# roller-shutter-controller.net
KiCad netlist of a schematic drawn in EAGLE
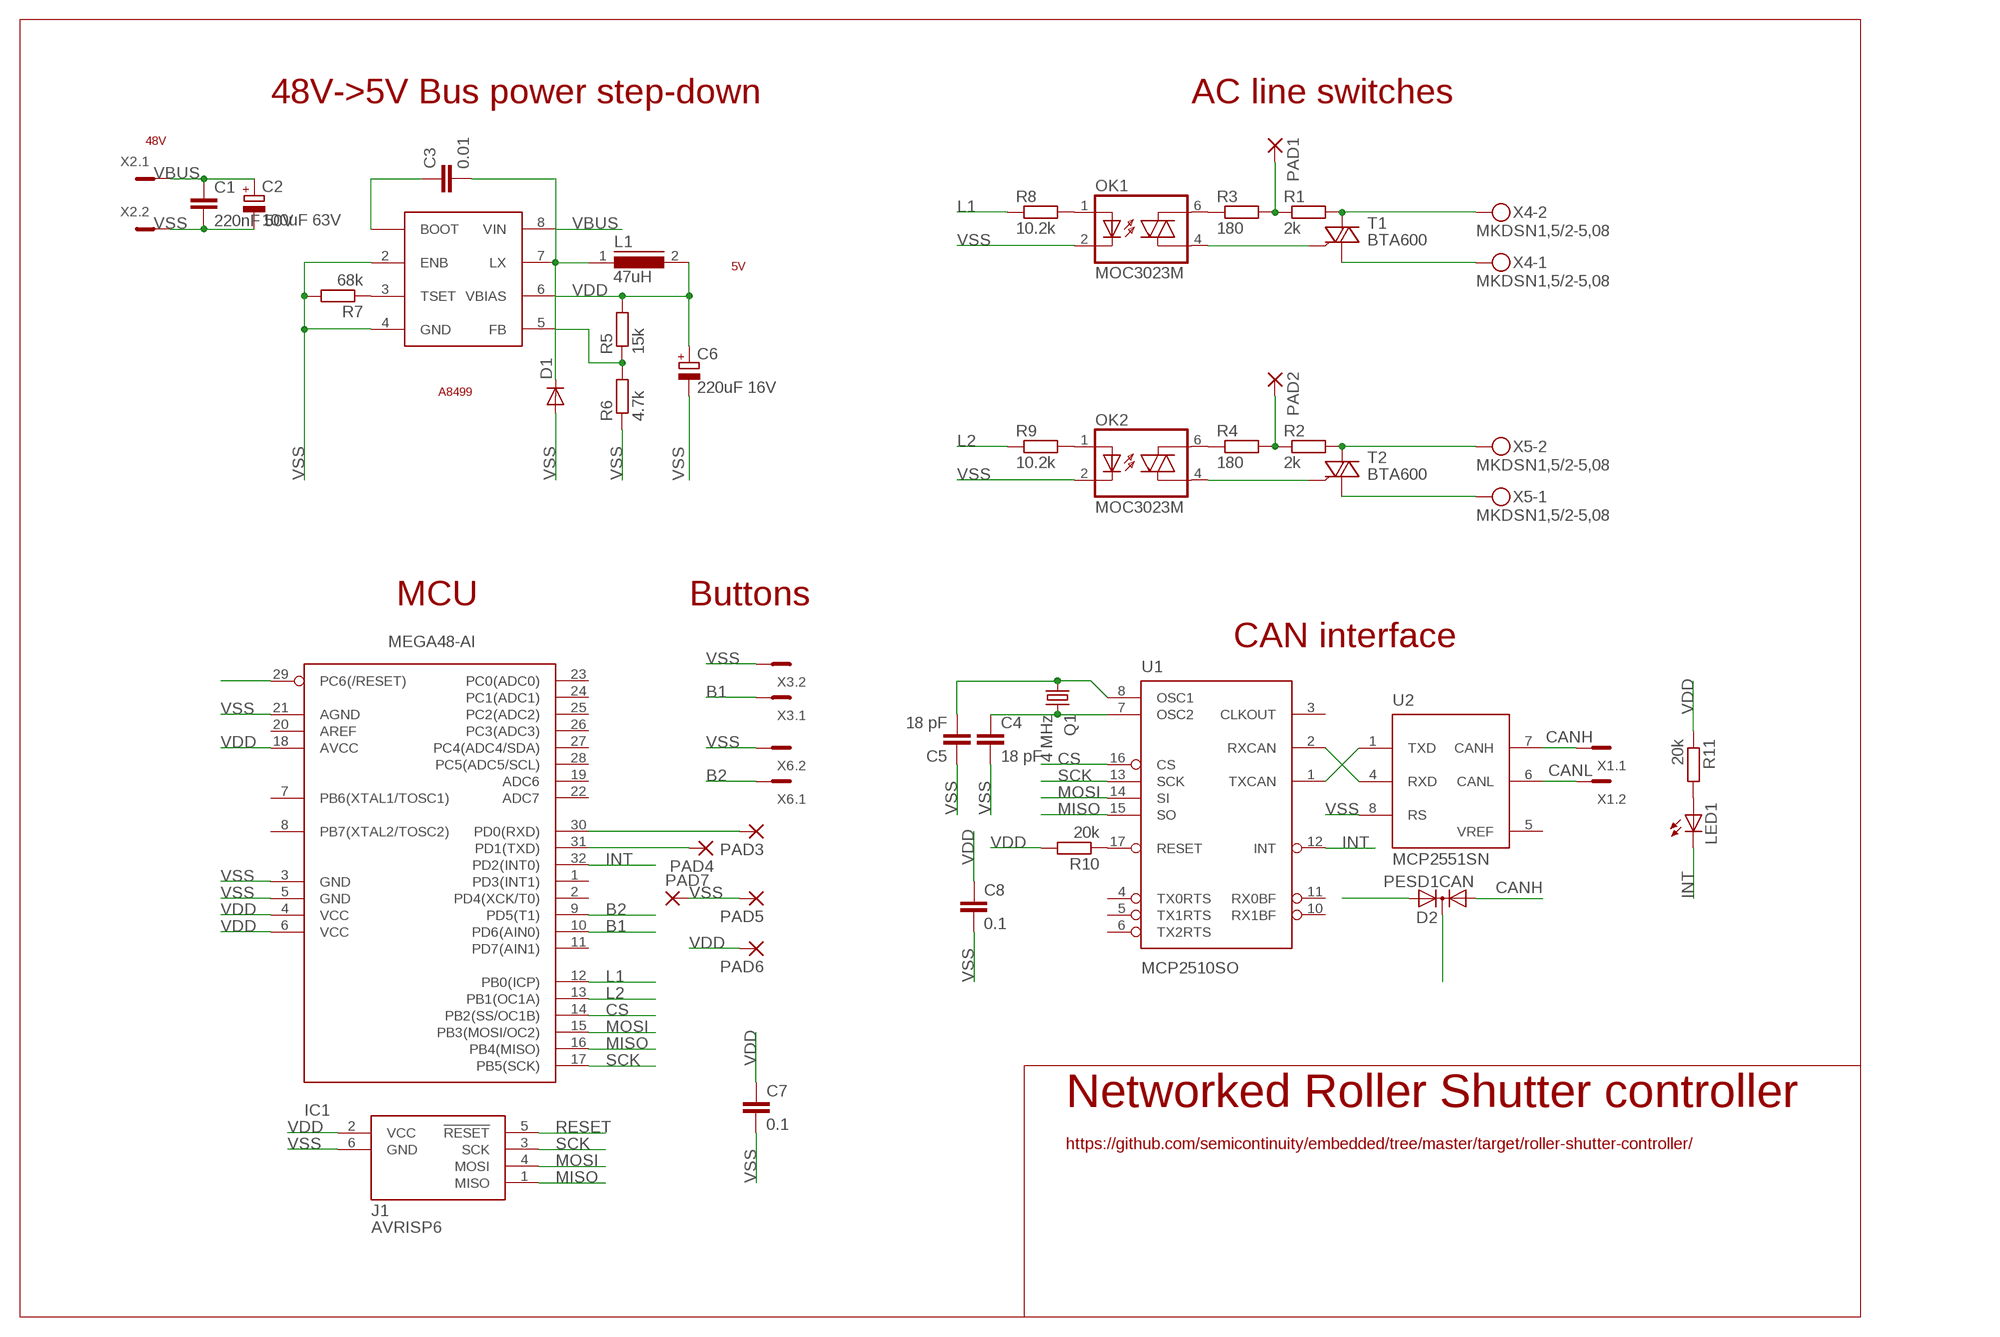
[diagram p0: schematic, sheet 1]

(export (version "E")
  (design (tool "Eeschema 10.0.6"))
  (components
    (comp (ref "C1")
      (value "220nF 50V")
      (footprint "eagle-import:C0805")
      (libsource (lib "eagle-import") (part "C-EUC0805"))
    )
    (comp (ref "C2")
      (value "100uF 63V")
      (footprint "eagle-import:153CLV-1010")
      (libsource (lib "eagle-import") (part "CPOL-EU153CLV-1010"))
    )
    (comp (ref "C3")
      (value "0.01")
      (footprint "eagle-import:C0805")
      (libsource (lib "eagle-import") (part "C-EUC0805"))
    )
    (comp (ref "C4")
      (value "18 pF")
      (footprint "eagle-import:C0805")
      (libsource (lib "eagle-import") (part "C-EUC0805"))
    )
    (comp (ref "C5")
      (value "18 pF")
      (footprint "eagle-import:C0805")
      (libsource (lib "eagle-import") (part "C-EUC0805"))
    )
    (comp (ref "C6")
      (value "220uF 16V")
      (footprint "eagle-import:153CLV-0605")
      (libsource (lib "eagle-import") (part "CPOL-EU153CLV-0605"))
    )
    (comp (ref "C7")
      (value "0.1")
      (footprint "eagle-import:C0805")
      (libsource (lib "eagle-import") (part "C-EUC0805"))
    )
    (comp (ref "C8")
      (value "0.1")
      (footprint "eagle-import:C0805")
      (libsource (lib "eagle-import") (part "C-EUC0805"))
    )
    (comp (ref "D1")
      (value "DIODE-SMB")
      (footprint "eagle-import:SMB")
      (libsource (lib "eagle-import") (part "DIODE-SMB"))
    )
    (comp (ref "D2")
      (value "PESD1CAN")
      (footprint "eagle-import:SOT323")
      (libsource (lib "eagle-import") (part "DIODEA2KSOT323"))
    )
    (comp (ref "IC1")
      (value "MEGA48-AI")
      (footprint "eagle-import:TQFP32-08")
      (libsource (lib "eagle-import") (part "MEGA8-AI"))
    )
    (comp (ref "J1")
      (value "AVRISP6")
      (footprint "eagle-import:CON6P2R")
      (libsource (lib "eagle-import") (part "AVRISP6"))
    )
    (comp (ref "L1")
      (value "47uH")
      (footprint "eagle-import:DR127")
      (libsource (lib "eagle-import") (part "DR127"))
    )
    (comp (ref "LED1")
      (value "LEDCHIP-LED0805")
      (footprint "eagle-import:CHIP-LED0805")
      (libsource (lib "eagle-import") (part "LEDCHIP-LED0805"))
    )
    (comp (ref "OK1")
      (value "MOC3023M")
      (footprint "eagle-import:DIL06")
      (libsource (lib "eagle-import") (part "MOC30M23"))
    )
    (comp (ref "OK2")
      (value "MOC3023M")
      (footprint "eagle-import:DIL06")
      (libsource (lib "eagle-import") (part "MOC30M23"))
    )
    (comp (ref "PAD1")
      (value "1,6/0,8")
      (footprint "eagle-import:1,6_0,8")
      (libsource (lib "eagle-import") (part "1,6/0,8"))
    )
    (comp (ref "PAD2")
      (value "1,6/0,8")
      (footprint "eagle-import:1,6_0,8")
      (libsource (lib "eagle-import") (part "1,6/0,8"))
    )
    (comp (ref "PAD3")
      (value "1,6/0,8")
      (footprint "eagle-import:1,6_0,8")
      (libsource (lib "eagle-import") (part "1,6/0,8"))
    )
    (comp (ref "PAD4")
      (value "1,6/0,8")
      (footprint "eagle-import:1,6_0,8")
      (libsource (lib "eagle-import") (part "1,6/0,8"))
    )
    (comp (ref "PAD5")
      (value "1,6/0,8")
      (footprint "eagle-import:1,6_0,8")
      (libsource (lib "eagle-import") (part "1,6/0,8"))
    )
    (comp (ref "PAD6")
      (value "1,6/0,8")
      (footprint "eagle-import:1,6_0,8")
      (libsource (lib "eagle-import") (part "1,6/0,8"))
    )
    (comp (ref "PAD7")
      (value "1,6/0,8")
      (footprint "eagle-import:1,6_0,8")
      (libsource (lib "eagle-import") (part "1,6/0,8"))
    )
    (comp (ref "Q1")
      (value "4 MHz")
      (footprint "eagle-import:HC49_S")
      (libsource (lib "eagle-import") (part "CRYSTALHC49S"))
    )
    (comp (ref "R1")
      (value "2k")
      (footprint "eagle-import:M0805")
      (libsource (lib "eagle-import") (part "R-EU_M0805"))
    )
    (comp (ref "R2")
      (value "2k")
      (footprint "eagle-import:M0805")
      (libsource (lib "eagle-import") (part "R-EU_M0805"))
    )
    (comp (ref "R3")
      (value "180")
      (footprint "eagle-import:M0805")
      (libsource (lib "eagle-import") (part "R-EU_M0805"))
    )
    (comp (ref "R4")
      (value "180")
      (footprint "eagle-import:M0805")
      (libsource (lib "eagle-import") (part "R-EU_M0805"))
    )
    (comp (ref "R5")
      (value "15k")
      (footprint "eagle-import:R0805")
      (libsource (lib "eagle-import") (part "R-EU_R0805"))
    )
    (comp (ref "R6")
      (value "4.7k")
      (footprint "eagle-import:R0805")
      (libsource (lib "eagle-import") (part "R-EU_R0805"))
    )
    (comp (ref "R7")
      (value "68k")
      (footprint "eagle-import:R0805")
      (libsource (lib "eagle-import") (part "R-EU_R0805"))
    )
    (comp (ref "R8")
      (value "10.2k")
      (footprint "eagle-import:R0805")
      (libsource (lib "eagle-import") (part "R-EU_R0805"))
    )
    (comp (ref "R9")
      (value "10.2k")
      (footprint "eagle-import:R0805")
      (libsource (lib "eagle-import") (part "R-EU_R0805"))
    )
    (comp (ref "R10")
      (value "20k")
      (footprint "eagle-import:R0805")
      (libsource (lib "eagle-import") (part "R-EU_R0805"))
    )
    (comp (ref "R11")
      (value "20k")
      (footprint "eagle-import:R0805")
      (libsource (lib "eagle-import") (part "R-EU_R0805"))
    )
    (comp (ref "T1")
      (value "BTA600")
      (footprint "eagle-import:TO220DS")
      (libsource (lib "eagle-import") (part "TIC225S"))
    )
    (comp (ref "T2")
      (value "BTA600")
      (footprint "eagle-import:TO220DS")
      (libsource (lib "eagle-import") (part "TIC225S"))
    )
    (comp (ref "U$1")
      (value "A8499")
      (footprint "eagle-import:SO08")
      (libsource (lib "eagle-import") (part "A8499SLJT"))
    )
    (comp (ref "U1")
      (value "MCP2510SO")
      (footprint "eagle-import:SO-18W")
      (libsource (lib "eagle-import") (part "MCP2510SO"))
    )
    (comp (ref "U2")
      (value "MCP2551SN")
      (footprint "eagle-import:SO-08")
      (libsource (lib "eagle-import") (part "MCP2551SN"))
    )
    (comp (ref "X1")
      (value "MCV2")
      (footprint "eagle-import:MCV2")
      (libsource (lib "eagle-import") (part "MCV2"))
    )
    (comp (ref "X2")
      (value "MCV2")
      (footprint "eagle-import:MCV2")
      (libsource (lib "eagle-import") (part "MCV2"))
    )
    (comp (ref "X3")
      (value "MCV2")
      (footprint "eagle-import:MCV2")
      (libsource (lib "eagle-import") (part "MCV2"))
    )
    (comp (ref "X4")
      (value "MKDSN1,5/2-5,08")
      (footprint "eagle-import:MKDSN1,5_2-5,08")
      (fields (field (name "MPN") "MKDSN 1,5/2-5.08"))
      (libsource (lib "eagle-import") (part "MKDSN1,5/2-5,08"))
    )
    (comp (ref "X5")
      (value "MKDSN1,5/2-5,08")
      (footprint "eagle-import:MKDSN1,5_2-5,08")
      (fields (field (name "MPN") "MKDSN 1,5/2-5.08"))
      (libsource (lib "eagle-import") (part "MKDSN1,5/2-5,08"))
    )
    (comp (ref "X6")
      (value "MCV2")
      (footprint "eagle-import:MCV2")
      (libsource (lib "eagle-import") (part "MCV2"))
    )
  )
  (nets
    (net (code "1") (name "/B1") (class "Default")
      (node (ref "IC1") (pin "10") (pinfunction "PD6(AIN0)_10") (pintype "bidirectional"))
      (node (ref "X3") (pin "1") (pinfunction "SK_1") (pintype "passive"))
    )
    (net (code "2") (name "/B2") (class "Default")
      (node (ref "IC1") (pin "9") (pinfunction "PD5(T1)_9") (pintype "bidirectional"))
      (node (ref "X6") (pin "1") (pinfunction "SK_1") (pintype "passive"))
    )
    (net (code "3") (name "/CANH") (class "Default")
      (node (ref "D2") (pin "1") (pinfunction "A1_1") (pintype "passive"))
      (node (ref "U2") (pin "7") (pinfunction "CANH_7") (pintype "bidirectional"))
      (node (ref "X1") (pin "1") (pinfunction "SK_1") (pintype "passive"))
    )
    (net (code "4") (name "/CANL") (class "Default")
      (node (ref "D2") (pin "2") (pinfunction "A2_2") (pintype "passive"))
      (node (ref "U2") (pin "6") (pinfunction "CANL_6") (pintype "bidirectional"))
      (node (ref "X1") (pin "2") (pinfunction "SK_2") (pintype "passive"))
    )
    (net (code "5") (name "/CS") (class "Default")
      (node (ref "IC1") (pin "14") (pinfunction "PB2(SS/OC1B)_14") (pintype "bidirectional"))
      (node (ref "U1") (pin "16") (pinfunction "CS_16") (pintype "input"))
    )
    (net (code "6") (name "/INT") (class "Default")
      (node (ref "IC1") (pin "32") (pinfunction "PD2(INT0)_32") (pintype "bidirectional"))
      (node (ref "LED1") (pin "C") (pinfunction "C_C") (pintype "passive"))
      (node (ref "U1") (pin "12") (pinfunction "INT_12") (pintype "output"))
    )
    (net (code "7") (name "/L1") (class "Default")
      (node (ref "IC1") (pin "12") (pinfunction "PB0(ICP)_12") (pintype "bidirectional"))
      (node (ref "R8") (pin "1") (pinfunction "1_1") (pintype "passive"))
    )
    (net (code "8") (name "/L2") (class "Default")
      (node (ref "IC1") (pin "13") (pinfunction "PB1(OC1A)_13") (pintype "bidirectional"))
      (node (ref "R9") (pin "1") (pinfunction "1_1") (pintype "passive"))
    )
    (net (code "9") (name "/MISO") (class "Default")
      (node (ref "IC1") (pin "16") (pinfunction "PB4(MISO)_16") (pintype "bidirectional"))
      (node (ref "J1") (pin "1") (pinfunction "MISO_1") (pintype "input"))
      (node (ref "U1") (pin "15") (pinfunction "SO_15") (pintype "output"))
    )
    (net (code "10") (name "/MOSI") (class "Default")
      (node (ref "IC1") (pin "15") (pinfunction "PB3(MOSI/OC2)_15") (pintype "bidirectional"))
      (node (ref "J1") (pin "4") (pinfunction "MOSI_4") (pintype "output"))
      (node (ref "U1") (pin "14") (pinfunction "SI_14") (pintype "input"))
    )
    (net (code "11") (name "/RESET") (class "Default")
      (node (ref "IC1") (pin "29") (pinfunction "PC6(/RESET)_29") (pintype "bidirectional"))
      (node (ref "J1") (pin "5") (pinfunction "~{RESET}_5") (pintype "output"))
    )
    (net (code "12") (name "/SCK") (class "Default")
      (node (ref "IC1") (pin "17") (pinfunction "PB5(SCK)_17") (pintype "bidirectional"))
      (node (ref "J1") (pin "3") (pinfunction "SCK_3") (pintype "output"))
      (node (ref "U1") (pin "13") (pinfunction "SCK_13") (pintype "input"))
    )
    (net (code "13") (name "/VBUS") (class "Default")
      (node (ref "C1") (pin "1") (pinfunction "1_1") (pintype "passive"))
      (node (ref "C2") (pin "+") (pinfunction "+_+") (pintype "passive"))
      (node (ref "U$1") (pin "8") (pinfunction "VIN_8") (pintype "power_in"))
      (node (ref "X2") (pin "1") (pinfunction "SK_1") (pintype "passive"))
    )
    (net (code "14") (name "/VDD") (class "Default")
      (node (ref "C6") (pin "+") (pinfunction "+_+") (pintype "passive"))
      (node (ref "C7") (pin "1") (pinfunction "1_1") (pintype "passive"))
      (node (ref "C8") (pin "1") (pinfunction "1_1") (pintype "passive"))
      (node (ref "IC1") (pin "18") (pinfunction "AVCC_18") (pintype "bidirectional"))
      (node (ref "IC1") (pin "4") (pinfunction "VCC_4") (pintype "bidirectional"))
      (node (ref "IC1") (pin "6") (pinfunction "VCC_6") (pintype "bidirectional"))
      (node (ref "J1") (pin "2") (pinfunction "VCC_2") (pintype "power_in"))
      (node (ref "L1") (pin "2") (pinfunction "2_2") (pintype "passive"))
      (node (ref "PAD6") (pin "1") (pinfunction "P_1") (pintype "passive"))
      (node (ref "R10") (pin "2") (pinfunction "2_2") (pintype "passive"))
      (node (ref "R11") (pin "1") (pinfunction "1_1") (pintype "passive"))
      (node (ref "R5") (pin "2") (pinfunction "2_2") (pintype "passive"))
      (node (ref "U$1") (pin "6") (pinfunction "VBIAS_6") (pintype "power_in"))
    )
    (net (code "15") (name "/VREF") (class "Default")
      (node (ref "U2") (pin "5") (pinfunction "VREF_5") (pintype "power_in"))
    )
    (net (code "16") (name "/VSS") (class "Default")
      (node (ref "C1") (pin "2") (pinfunction "2_2") (pintype "passive"))
      (node (ref "C2") (pin "-") (pinfunction "-_-") (pintype "passive"))
      (node (ref "C4") (pin "2") (pinfunction "2_2") (pintype "passive"))
      (node (ref "C5") (pin "1") (pinfunction "1_1") (pintype "passive"))
      (node (ref "C6") (pin "-") (pinfunction "-_-") (pintype "passive"))
      (node (ref "C7") (pin "2") (pinfunction "2_2") (pintype "passive"))
      (node (ref "C8") (pin "2") (pinfunction "2_2") (pintype "passive"))
      (node (ref "D1") (pin "A") (pinfunction "A_A") (pintype "passive"))
      (node (ref "D2") (pin "3") (pinfunction "C_3") (pintype "passive"))
      (node (ref "IC1") (pin "21") (pinfunction "AGND_21") (pintype "bidirectional"))
      (node (ref "IC1") (pin "3") (pinfunction "GND_3") (pintype "bidirectional"))
      (node (ref "IC1") (pin "5") (pinfunction "GND_5") (pintype "bidirectional"))
      (node (ref "J1") (pin "6") (pinfunction "GND_6") (pintype "power_in"))
      (node (ref "OK1") (pin "2") (pinfunction "C_2") (pintype "passive"))
      (node (ref "OK2") (pin "2") (pinfunction "C_2") (pintype "passive"))
      (node (ref "PAD5") (pin "1") (pinfunction "P_1") (pintype "passive"))
      (node (ref "PAD7") (pin "1") (pinfunction "P_1") (pintype "passive"))
      (node (ref "R6") (pin "1") (pinfunction "1_1") (pintype "passive"))
      (node (ref "R7") (pin "2") (pinfunction "2_2") (pintype "passive"))
      (node (ref "U$1") (pin "2") (pinfunction "ENB_2") (pintype "power_in"))
      (node (ref "U$1") (pin "4") (pinfunction "GND_4") (pintype "power_in"))
      (node (ref "U2") (pin "8") (pinfunction "RS_8") (pintype "input"))
      (node (ref "X2") (pin "2") (pinfunction "SK_2") (pintype "passive"))
      (node (ref "X3") (pin "2") (pinfunction "SK_2") (pintype "passive"))
      (node (ref "X6") (pin "2") (pinfunction "SK_2") (pintype "passive"))
    )
    (net (code "17") (name "Net-(IC1-PD0(RXD))") (class "Default")
      (node (ref "IC1") (pin "30") (pinfunction "PD0(RXD)_30") (pintype "bidirectional"))
      (node (ref "PAD3") (pin "1") (pinfunction "P_1") (pintype "passive"))
    )
    (net (code "18") (name "Net-(IC1-PD1(TXD))") (class "Default")
      (node (ref "IC1") (pin "31") (pinfunction "PD1(TXD)_31") (pintype "bidirectional"))
      (node (ref "PAD4") (pin "1") (pinfunction "P_1") (pintype "passive"))
    )
    (net (code "19") (name "Net-(LED1-PadA)") (class "Default")
      (node (ref "LED1") (pin "A") (pinfunction "A_A") (pintype "passive"))
      (node (ref "R11") (pin "2") (pinfunction "2_2") (pintype "passive"))
    )
    (net (code "20") (name "Net-(OK1-A)") (class "Default")
      (node (ref "OK1") (pin "1") (pinfunction "A_1") (pintype "passive"))
      (node (ref "R8") (pin "2") (pinfunction "2_2") (pintype "passive"))
    )
    (net (code "21") (name "Net-(OK1-A1)") (class "Default")
      (node (ref "OK1") (pin "4") (pinfunction "A1_4") (pintype "passive"))
      (node (ref "T1") (pin "G") (pinfunction "G_G") (pintype "passive"))
    )
    (net (code "22") (name "Net-(OK1-A2)") (class "Default")
      (node (ref "OK1") (pin "6") (pinfunction "A2_6") (pintype "passive"))
      (node (ref "R3") (pin "1") (pinfunction "1_1") (pintype "passive"))
    )
    (net (code "23") (name "Net-(OK2-A)") (class "Default")
      (node (ref "OK2") (pin "1") (pinfunction "A_1") (pintype "passive"))
      (node (ref "R9") (pin "2") (pinfunction "2_2") (pintype "passive"))
    )
    (net (code "24") (name "Net-(OK2-A1)") (class "Default")
      (node (ref "OK2") (pin "4") (pinfunction "A1_4") (pintype "passive"))
      (node (ref "T2") (pin "G") (pinfunction "G_G") (pintype "passive"))
    )
    (net (code "25") (name "Net-(OK2-A2)") (class "Default")
      (node (ref "OK2") (pin "6") (pinfunction "A2_6") (pintype "passive"))
      (node (ref "R4") (pin "1") (pinfunction "1_1") (pintype "passive"))
    )
    (net (code "26") (name "Net-(PAD1-P)") (class "Default")
      (node (ref "PAD1") (pin "1") (pinfunction "P_1") (pintype "passive"))
      (node (ref "R1") (pin "1") (pinfunction "1_1") (pintype "passive"))
      (node (ref "R3") (pin "2") (pinfunction "2_2") (pintype "passive"))
    )
    (net (code "27") (name "Net-(PAD2-P)") (class "Default")
      (node (ref "PAD2") (pin "1") (pinfunction "P_1") (pintype "passive"))
      (node (ref "R2") (pin "1") (pinfunction "1_1") (pintype "passive"))
      (node (ref "R4") (pin "2") (pinfunction "2_2") (pintype "passive"))
    )
    (net (code "28") (name "Net-(U$1-BOOT)") (class "Default")
      (node (ref "C3") (pin "1") (pinfunction "1_1") (pintype "passive"))
      (node (ref "U$1") (pin "1") (pinfunction "BOOT_1") (pintype "power_in"))
    )
    (net (code "29") (name "Net-(U$1-FB)") (class "Default")
      (node (ref "R5") (pin "1") (pinfunction "1_1") (pintype "passive"))
      (node (ref "R6") (pin "2") (pinfunction "2_2") (pintype "passive"))
      (node (ref "U$1") (pin "5") (pinfunction "FB_5") (pintype "power_in"))
    )
    (net (code "30") (name "Net-(U$1-LX)") (class "Default")
      (node (ref "C3") (pin "2") (pinfunction "2_2") (pintype "passive"))
      (node (ref "D1") (pin "C") (pinfunction "C_C") (pintype "passive"))
      (node (ref "L1") (pin "1") (pinfunction "1_1") (pintype "passive"))
      (node (ref "U$1") (pin "7") (pinfunction "LX_7") (pintype "power_in"))
    )
    (net (code "31") (name "Net-(U$1-TSET)") (class "Default")
      (node (ref "R7") (pin "1") (pinfunction "1_1") (pintype "passive"))
      (node (ref "U$1") (pin "3") (pinfunction "TSET_3") (pintype "power_in"))
    )
    (net (code "32") (name "Net-(U1A-OSC1)") (class "Default")
      (node (ref "C5") (pin "2") (pinfunction "2_2") (pintype "passive"))
      (node (ref "Q1") (pin "1") (pinfunction "1_1") (pintype "passive"))
      (node (ref "U1") (pin "8") (pinfunction "OSC1_8") (pintype "input"))
    )
    (net (code "33") (name "Net-(U1A-OSC2)") (class "Default")
      (node (ref "C4") (pin "1") (pinfunction "1_1") (pintype "passive"))
      (node (ref "Q1") (pin "2") (pinfunction "2_2") (pintype "passive"))
      (node (ref "U1") (pin "7") (pinfunction "OSC2_7") (pintype "output"))
    )
    (net (code "34") (name "Net-(U1A-RESET)") (class "Default")
      (node (ref "R10") (pin "1") (pinfunction "1_1") (pintype "passive"))
      (node (ref "U1") (pin "17") (pinfunction "RESET_17") (pintype "input"))
    )
    (net (code "35") (name "Net-(U1A-RXCAN)") (class "Default")
      (node (ref "U1") (pin "2") (pinfunction "RXCAN_2") (pintype "input"))
      (node (ref "U2") (pin "4") (pinfunction "RXD_4") (pintype "output"))
    )
    (net (code "36") (name "Net-(U1A-TXCAN)") (class "Default")
      (node (ref "U1") (pin "1") (pinfunction "TXCAN_1") (pintype "output"))
      (node (ref "U2") (pin "1") (pinfunction "TXD_1") (pintype "input"))
    )
    (net (code "37") (name "Net-(X4A-KL)") (class "Default")
      (node (ref "T1") (pin "A1") (pinfunction "A1_A1") (pintype "passive"))
      (node (ref "X4") (pin "1") (pinfunction "KL_1") (pintype "passive"))
    )
    (net (code "38") (name "Net-(X4B-KL)") (class "Default")
      (node (ref "R1") (pin "2") (pinfunction "2_2") (pintype "passive"))
      (node (ref "T1") (pin "A2") (pinfunction "A2_A2") (pintype "passive"))
      (node (ref "X4") (pin "2") (pinfunction "KL_2") (pintype "passive"))
    )
    (net (code "39") (name "Net-(X5A-KL)") (class "Default")
      (node (ref "T2") (pin "A1") (pinfunction "A1_A1") (pintype "passive"))
      (node (ref "X5") (pin "1") (pinfunction "KL_1") (pintype "passive"))
    )
    (net (code "40") (name "Net-(X5B-KL)") (class "Default")
      (node (ref "R2") (pin "2") (pinfunction "2_2") (pintype "passive"))
      (node (ref "T2") (pin "A2") (pinfunction "A2_A2") (pintype "passive"))
      (node (ref "X5") (pin "2") (pinfunction "KL_2") (pintype "passive"))
    )
    (net (code "41") (name "unconnected-(IC1-ADC6-Pad19)") (class "Default")
      (node (ref "IC1") (pin "19") (pinfunction "ADC6_19") (pintype "bidirectional"))
    )
    (net (code "42") (name "unconnected-(IC1-ADC7-Pad22)") (class "Default")
      (node (ref "IC1") (pin "22") (pinfunction "ADC7_22") (pintype "bidirectional"))
    )
    (net (code "43") (name "unconnected-(IC1-AREF-Pad20)") (class "Default")
      (node (ref "IC1") (pin "20") (pinfunction "AREF_20") (pintype "bidirectional"))
    )
    (net (code "44") (name "unconnected-(IC1-PB6(XTAL1{slash}TOSC1)-Pad7)") (class "Default")
      (node (ref "IC1") (pin "7") (pinfunction "PB6(XTAL1/TOSC1)_7") (pintype "bidirectional"))
    )
    (net (code "45") (name "unconnected-(IC1-PB7(XTAL2{slash}TOSC2)-Pad8)") (class "Default")
      (node (ref "IC1") (pin "8") (pinfunction "PB7(XTAL2/TOSC2)_8") (pintype "bidirectional"))
    )
    (net (code "46") (name "unconnected-(IC1-PC0(ADC0)-Pad23)") (class "Default")
      (node (ref "IC1") (pin "23") (pinfunction "PC0(ADC0)_23") (pintype "bidirectional"))
    )
    (net (code "47") (name "unconnected-(IC1-PC1(ADC1)-Pad24)") (class "Default")
      (node (ref "IC1") (pin "24") (pinfunction "PC1(ADC1)_24") (pintype "bidirectional"))
    )
    (net (code "48") (name "unconnected-(IC1-PC2(ADC2)-Pad25)") (class "Default")
      (node (ref "IC1") (pin "25") (pinfunction "PC2(ADC2)_25") (pintype "bidirectional"))
    )
    (net (code "49") (name "unconnected-(IC1-PC3(ADC3)-Pad26)") (class "Default")
      (node (ref "IC1") (pin "26") (pinfunction "PC3(ADC3)_26") (pintype "bidirectional"))
    )
    (net (code "50") (name "unconnected-(IC1-PC4(ADC4{slash}SDA)-Pad27)") (class "Default")
      (node (ref "IC1") (pin "27") (pinfunction "PC4(ADC4/SDA)_27") (pintype "bidirectional"))
    )
    (net (code "51") (name "unconnected-(IC1-PC5(ADC5{slash}SCL)-Pad28)") (class "Default")
      (node (ref "IC1") (pin "28") (pinfunction "PC5(ADC5/SCL)_28") (pintype "bidirectional"))
    )
    (net (code "52") (name "unconnected-(IC1-PD3(INT1)-Pad1)") (class "Default")
      (node (ref "IC1") (pin "1") (pinfunction "PD3(INT1)_1") (pintype "bidirectional"))
    )
    (net (code "53") (name "unconnected-(IC1-PD4(XCK{slash}T0)-Pad2)") (class "Default")
      (node (ref "IC1") (pin "2") (pinfunction "PD4(XCK/T0)_2") (pintype "bidirectional"))
    )
    (net (code "54") (name "unconnected-(IC1-PD7(AIN1)-Pad11)") (class "Default")
      (node (ref "IC1") (pin "11") (pinfunction "PD7(AIN1)_11") (pintype "bidirectional"))
    )
    (net (code "55") (name "unconnected-(U1A-CLKOUT-Pad3)") (class "Default")
      (node (ref "U1") (pin "3") (pinfunction "CLKOUT_3") (pintype "output"))
    )
    (net (code "56") (name "unconnected-(U1A-RX0BF-Pad11)") (class "Default")
      (node (ref "U1") (pin "11") (pinfunction "RX0BF_11") (pintype "output"))
    )
    (net (code "57") (name "unconnected-(U1A-RX1BF-Pad10)") (class "Default")
      (node (ref "U1") (pin "10") (pinfunction "RX1BF_10") (pintype "output"))
    )
    (net (code "58") (name "unconnected-(U1A-TX0RTS-Pad4)") (class "Default")
      (node (ref "U1") (pin "4") (pinfunction "TX0RTS_4") (pintype "input"))
    )
    (net (code "59") (name "unconnected-(U1A-TX1RTS-Pad5)") (class "Default")
      (node (ref "U1") (pin "5") (pinfunction "TX1RTS_5") (pintype "input"))
    )
    (net (code "60") (name "unconnected-(U1A-TX2RTS-Pad6)") (class "Default")
      (node (ref "U1") (pin "6") (pinfunction "TX2RTS_6") (pintype "input"))
    )
  )
)
